# multivibrator.net
KiCad netlist of a schematic drawn in Altium Designer
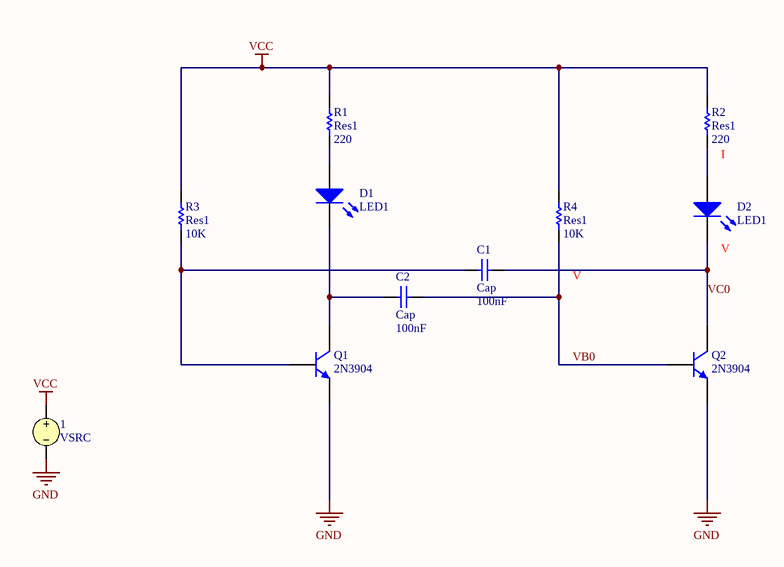
[diagram p0: multivibrator.SchDoc]

(export (version "E")
  (design (tool "Eeschema 10.0.6"))
  (components
    (comp (ref "1")
      (value "VSRC")
      (description "Voltage Source")
      (fields (field (name "PUBLISHER") "Altium Limited"))
      (libsource (lib "Simulation Sources") (part "VSRC"))
    )
    (comp (ref "C1")
      (value "Cap")
      (footprint "RAD-0.3")
      (description "Capacitor")
      (fields (field (name "ALTIUM_VALUE") "100nF") (field (name "PUBLISHER") "Altium Limited"))
      (libsource (lib "Miscellaneous Devices") (part "Cap"))
    )
    (comp (ref "C2")
      (value "Cap")
      (footprint "RAD-0.3")
      (description "Capacitor")
      (fields (field (name "ALTIUM_VALUE") "100nF") (field (name "PUBLISHER") "Altium Limited"))
      (libsource (lib "Miscellaneous Devices") (part "Cap"))
    )
    (comp (ref "D1")
      (value "LED1")
      (footprint "LED-1")
      (description "Typical RED GaAs LED")
      (fields (field (name "PUBLISHER") "Altium Limited"))
      (libsource (lib "Miscellaneous Devices") (part "LED1"))
    )
    (comp (ref "D2")
      (value "LED1")
      (footprint "LED-1")
      (description "Typical RED GaAs LED")
      (fields (field (name "PUBLISHER") "Altium Limited"))
      (libsource (lib "Miscellaneous Devices") (part "LED1"))
    )
    (comp (ref "Q1")
      (value "2N3904")
      (footprint "TO-92A")
      (description "NPN General Purpose Amplifier")
      (fields (field (name "PUBLISHER") "Altium Limited"))
      (libsource (lib "Miscellaneous Devices") (part "2N3904"))
    )
    (comp (ref "Q2")
      (value "2N3904")
      (footprint "TO-92A")
      (description "NPN General Purpose Amplifier")
      (fields (field (name "PUBLISHER") "Altium Limited"))
      (libsource (lib "Miscellaneous Devices") (part "2N3904"))
    )
    (comp (ref "R1")
      (value "Res1")
      (footprint "AXIAL-0.3")
      (description "Resistor")
      (fields (field (name "ALTIUM_VALUE") "220") (field (name "PUBLISHER") "Altium Limited"))
      (libsource (lib "Miscellaneous Devices") (part "Res1"))
    )
    (comp (ref "R2")
      (value "Res1")
      (footprint "AXIAL-0.3")
      (description "Resistor")
      (fields (field (name "ALTIUM_VALUE") "220") (field (name "PUBLISHER") "Altium Limited"))
      (libsource (lib "Miscellaneous Devices") (part "Res1"))
    )
    (comp (ref "R3")
      (value "Res1")
      (footprint "AXIAL-0.3")
      (description "Resistor")
      (fields (field (name "ALTIUM_VALUE") "10K") (field (name "PUBLISHER") "Altium Limited"))
      (libsource (lib "Miscellaneous Devices") (part "Res1"))
    )
    (comp (ref "R4")
      (value "Res1")
      (footprint "AXIAL-0.3")
      (description "Resistor")
      (fields (field (name "ALTIUM_VALUE") "10K") (field (name "PUBLISHER") "Altium Limited"))
      (libsource (lib "Miscellaneous Devices") (part "Res1"))
    )
  )
  (nets
    (net (code "1") (name "/VB0") (class "Default")
      (node (ref "C2") (pin "2") (pinfunction "2_2") (pintype "passive"))
      (node (ref "Q2") (pin "2") (pinfunction "B_2") (pintype "passive"))
      (node (ref "R4") (pin "1") (pinfunction "1_1") (pintype "passive"))
    )
    (net (code "2") (name "/VC0") (class "Default")
      (node (ref "C1") (pin "2") (pinfunction "2_2") (pintype "passive"))
      (node (ref "D2") (pin "2") (pinfunction "K_2") (pintype "passive"))
      (node (ref "Q2") (pin "3") (pinfunction "C_3") (pintype "passive"))
    )
    (net (code "3") (name "GND") (class "Default")
      (node (ref "1") (pin "2") (pinfunction "2_2") (pintype "passive"))
      (node (ref "Q1") (pin "1") (pinfunction "E_1") (pintype "passive"))
      (node (ref "Q2") (pin "1") (pinfunction "E_1") (pintype "passive"))
    )
    (net (code "4") (name "Net-(D1-A)") (class "Default")
      (node (ref "D1") (pin "1") (pinfunction "A_1") (pintype "passive"))
      (node (ref "R1") (pin "1") (pinfunction "1_1") (pintype "passive"))
    )
    (net (code "5") (name "Net-(D1-K)") (class "Default")
      (node (ref "C2") (pin "1") (pinfunction "1_1") (pintype "passive"))
      (node (ref "D1") (pin "2") (pinfunction "K_2") (pintype "passive"))
      (node (ref "Q1") (pin "3") (pinfunction "C_3") (pintype "passive"))
    )
    (net (code "6") (name "Net-(D2-A)") (class "Default")
      (node (ref "D2") (pin "1") (pinfunction "A_1") (pintype "passive"))
      (node (ref "R2") (pin "1") (pinfunction "1_1") (pintype "passive"))
    )
    (net (code "7") (name "Net-(Q1-B)") (class "Default")
      (node (ref "C1") (pin "1") (pinfunction "1_1") (pintype "passive"))
      (node (ref "Q1") (pin "2") (pinfunction "B_2") (pintype "passive"))
      (node (ref "R3") (pin "1") (pinfunction "1_1") (pintype "passive"))
    )
    (net (code "8") (name "VCC") (class "Default")
      (node (ref "1") (pin "1") (pinfunction "1_1") (pintype "passive"))
      (node (ref "R1") (pin "2") (pinfunction "2_2") (pintype "passive"))
      (node (ref "R2") (pin "2") (pinfunction "2_2") (pintype "passive"))
      (node (ref "R3") (pin "2") (pinfunction "2_2") (pintype "passive"))
      (node (ref "R4") (pin "2") (pinfunction "2_2") (pintype "passive"))
    )
  )
)
